# ArmRobot.net
KiCad netlist of a schematic drawn in EasyEDA Pro
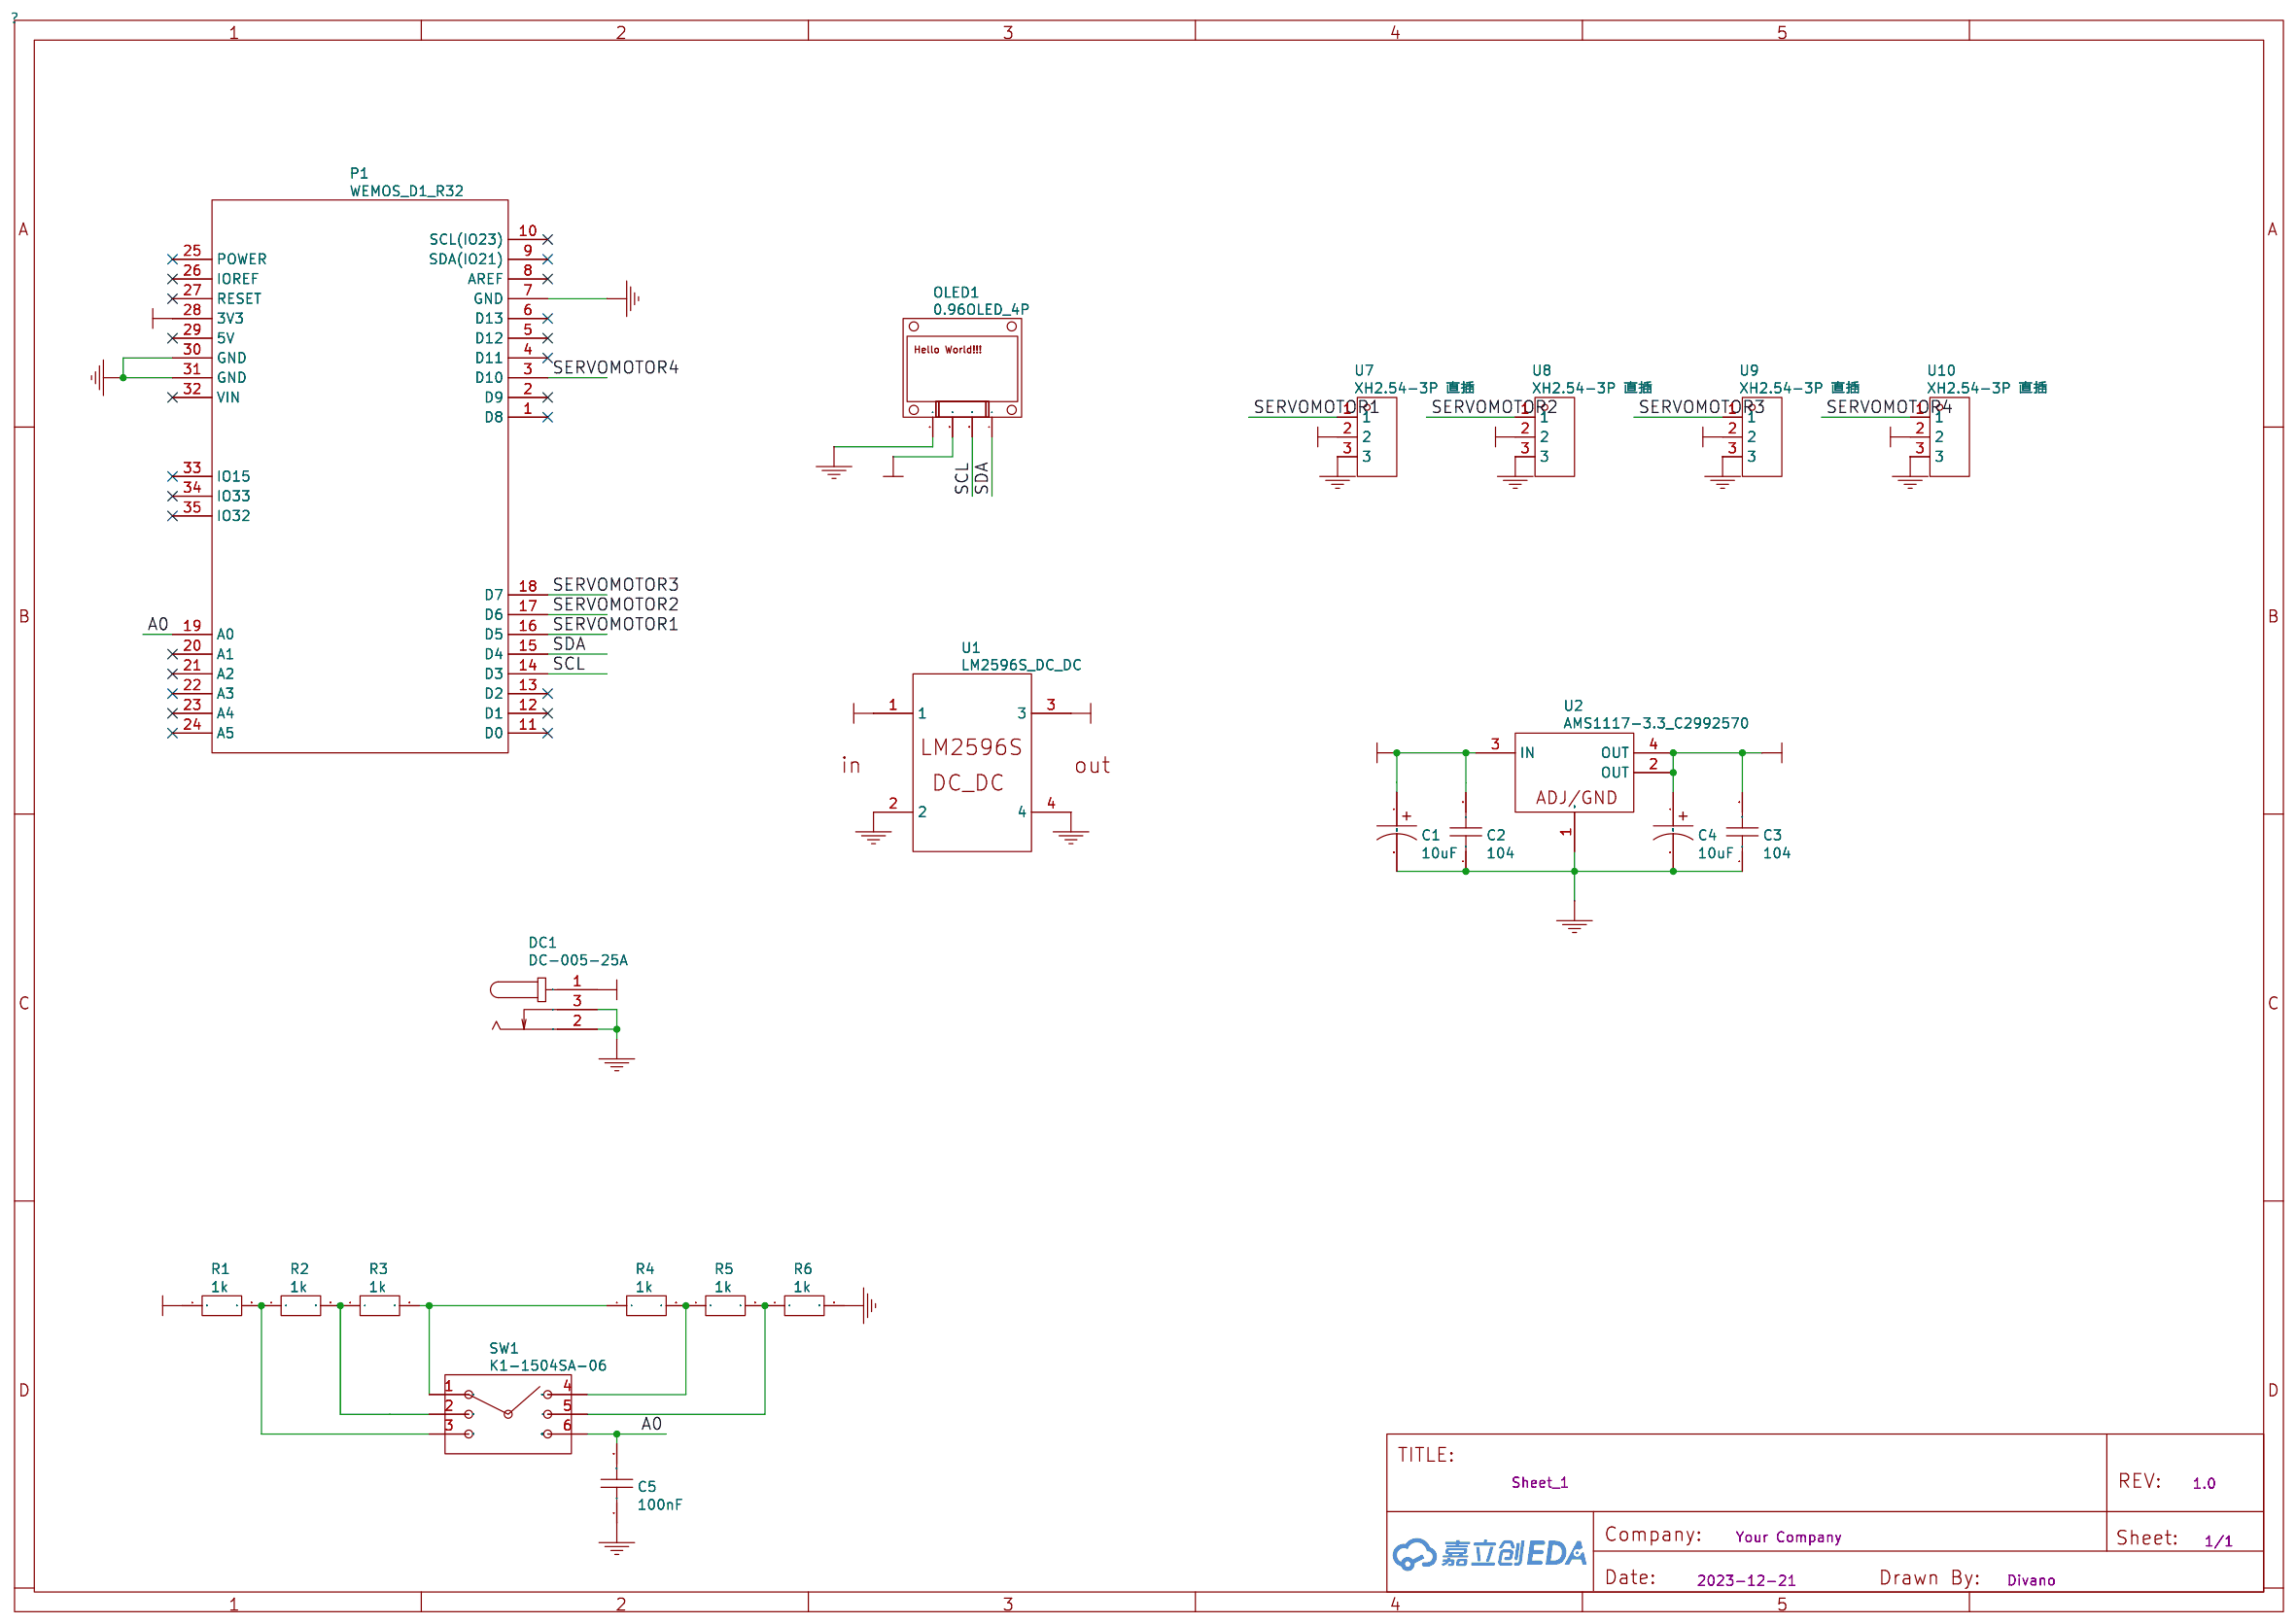
[diagram p0: schematic sheet]

(export (version "E")
  (design (tool "Eeschema 10.0.6"))
  (components
    (comp (ref "C1")
      (value "10uF")
      (footprint "easyedapro:CASE-A_3216")
      (libsource (lib "easyedapro") (part "10uF"))
    )
    (comp (ref "C2") (value "104") (footprint "easyedapro:C0805") (libsource (lib "easyedapro") (part "104")))
    (comp (ref "C3") (value "104") (footprint "easyedapro:C0805") (libsource (lib "easyedapro") (part "104")))
    (comp (ref "C4")
      (value "10uF")
      (footprint "easyedapro:CASE-A_3216")
      (libsource (lib "easyedapro") (part "10uF"))
    )
    (comp (ref "C5")
      (value "100nF")
      (footprint "easyedapro:C0805")
      (libsource (lib "easyedapro") (part "100nF"))
    )
    (comp (ref "DC1")
      (value "DC-005-25A")
      (footprint "easyedapro:DC-IN-TH_DC005")
      (fields (field (name "Manufacturer") "HRO"))
      (libsource (lib "easyedapro") (part "DC-005-25A"))
    )
    (comp (ref "OLED1")
      (value "0.96OLED_4P")
      (footprint "easyedapro:0.96OLED_4P")
      (libsource (lib "easyedapro") (part "0.96OLED_4P"))
    )
    (comp (ref "P1")
      (value "WEMOS_D1_R32")
      (footprint "easyedapro:WEMOS_D1_R32")
      (fields (field (name "Manufacturer Part") "NA"))
      (libsource (lib "easyedapro") (part "WEMOS_D1_R32"))
    )
    (comp (ref "R1") (value "1k") (footprint "easyedapro:R0805") (libsource (lib "easyedapro") (part "1k")))
    (comp (ref "R2") (value "1k") (footprint "easyedapro:R0805") (libsource (lib "easyedapro") (part "1k")))
    (comp (ref "R3") (value "1k") (footprint "easyedapro:R0805") (libsource (lib "easyedapro") (part "1k")))
    (comp (ref "R4") (value "1k") (footprint "easyedapro:R0805") (libsource (lib "easyedapro") (part "1k")))
    (comp (ref "R5") (value "1k") (footprint "easyedapro:R0805") (libsource (lib "easyedapro") (part "1k")))
    (comp (ref "R6") (value "1k") (footprint "easyedapro:R0805") (libsource (lib "easyedapro") (part "1k")))
    (comp (ref "SW1")
      (value "K1-1504SA-06")
      (footprint "easyedapro:SW-SMD_K1-1504SA-06")
      (fields (field (name "Manufacturer") "韩国韩荣"))
      (libsource (lib "easyedapro") (part "K1-1504SA-06"))
    )
    (comp (ref "U1")
      (value "LM2596S_DC_DC")
      (footprint "easyedapro:LM2596S_DC_DC")
      (libsource (lib "easyedapro") (part "LM2596S_DC_DC"))
    )
    (comp (ref "U2")
      (value "AMS1117-3.3_C2992570")
      (footprint "easyedapro:SOT-223-3_L6.4-W3.5-P2.30-LS7.0-BR")
      (fields (field (name "Manufacturer Part") "AMS1117-3.3") (field (name "Manufacturer") "国芯佳品"))
      (libsource (lib "easyedapro") (part "AMS1117-3.3_C2992570"))
    )
    (comp (ref "U7")
      (value "XH2.54-3P 直插")
      (footprint "easyedapro:CONN-TH_XH2.54-3P")
      (libsource (lib "easyedapro") (part "XH2.54-3P 直插"))
    )
    (comp (ref "U8")
      (value "XH2.54-3P 直插")
      (footprint "easyedapro:CONN-TH_XH2.54-3P")
      (libsource (lib "easyedapro") (part "XH2.54-3P 直插"))
    )
    (comp (ref "U9")
      (value "XH2.54-3P 直插")
      (footprint "easyedapro:CONN-TH_XH2.54-3P")
      (libsource (lib "easyedapro") (part "XH2.54-3P 直插"))
    )
    (comp (ref "U10")
      (value "XH2.54-3P 直插")
      (footprint "easyedapro:CONN-TH_XH2.54-3P")
      (libsource (lib "easyedapro") (part "XH2.54-3P 直插"))
    )
  )
  (nets
    (net (code "1") (name "+3.3V") (class "Default")
      (node (ref "C3") (pin "2") (pinfunction "2_2") (pintype "input"))
      (node (ref "C4") (pin "1") (pinfunction "1_1") (pintype "input"))
      (node (ref "OLED1") (pin "2") (pinfunction "2_2") (pintype "input"))
      (node (ref "P1") (pin "28") (pinfunction "3V3_28") (pintype "input"))
      (node (ref "R1") (pin "1") (pinfunction "1_1") (pintype "input"))
      (node (ref "U2") (pin "2") (pinfunction "OUT_2") (pintype "input"))
      (node (ref "U2") (pin "4") (pinfunction "OUT_4") (pintype "input"))
    )
    (net (code "2") (name "+5V") (class "Default")
      (node (ref "C1") (pin "1") (pinfunction "1_1") (pintype "input"))
      (node (ref "C2") (pin "2") (pinfunction "2_2") (pintype "input"))
      (node (ref "U1") (pin "3") (pinfunction "3_3") (pintype "input"))
      (node (ref "U10") (pin "2") (pinfunction "2_2") (pintype "input"))
      (node (ref "U2") (pin "3") (pinfunction "IN_3") (pintype "input"))
      (node (ref "U7") (pin "2") (pinfunction "2_2") (pintype "input"))
      (node (ref "U8") (pin "2") (pinfunction "2_2") (pintype "input"))
      (node (ref "U9") (pin "2") (pinfunction "2_2") (pintype "input"))
    )
    (net (code "3") (name "+12V") (class "Default")
      (node (ref "DC1") (pin "1") (pinfunction "1_1") (pintype "input"))
      (node (ref "U1") (pin "1") (pinfunction "1_1") (pintype "input"))
    )
    (net (code "4") (name "/A0") (class "Default")
      (node (ref "C5") (pin "2") (pinfunction "2_2") (pintype "input"))
      (node (ref "P1") (pin "19") (pinfunction "A0_19") (pintype "input"))
      (node (ref "SW1") (pin "6") (pinfunction "COMMON_6") (pintype "input"))
    )
    (net (code "5") (name "/SCL") (class "Default")
      (node (ref "OLED1") (pin "3") (pinfunction "3_3") (pintype "input"))
      (node (ref "P1") (pin "14") (pinfunction "D3_14") (pintype "input"))
    )
    (net (code "6") (name "/SDA") (class "Default")
      (node (ref "OLED1") (pin "4") (pinfunction "4_4") (pintype "input"))
      (node (ref "P1") (pin "15") (pinfunction "D4_15") (pintype "input"))
    )
    (net (code "7") (name "/SERVOMOTOR1") (class "Default")
      (node (ref "P1") (pin "16") (pinfunction "D5_16") (pintype "input"))
      (node (ref "U7") (pin "1") (pinfunction "1_1") (pintype "input"))
    )
    (net (code "8") (name "/SERVOMOTOR2") (class "Default")
      (node (ref "P1") (pin "17") (pinfunction "D6_17") (pintype "input"))
      (node (ref "U8") (pin "1") (pinfunction "1_1") (pintype "input"))
    )
    (net (code "9") (name "/SERVOMOTOR3") (class "Default")
      (node (ref "P1") (pin "18") (pinfunction "D7_18") (pintype "input"))
      (node (ref "U9") (pin "1") (pinfunction "1_1") (pintype "input"))
    )
    (net (code "10") (name "/SERVOMOTOR4") (class "Default")
      (node (ref "P1") (pin "3") (pinfunction "D10_3") (pintype "input"))
      (node (ref "U10") (pin "1") (pinfunction "1_1") (pintype "input"))
    )
    (net (code "11") (name "GND") (class "Default")
      (node (ref "C1") (pin "2") (pinfunction "2_2") (pintype "input"))
      (node (ref "C2") (pin "1") (pinfunction "1_1") (pintype "input"))
      (node (ref "C3") (pin "1") (pinfunction "1_1") (pintype "input"))
      (node (ref "C4") (pin "2") (pinfunction "2_2") (pintype "input"))
      (node (ref "C5") (pin "1") (pinfunction "1_1") (pintype "input"))
      (node (ref "DC1") (pin "2") (pinfunction "2_2") (pintype "input"))
      (node (ref "DC1") (pin "3") (pinfunction "3_3") (pintype "input"))
      (node (ref "OLED1") (pin "1") (pinfunction "1_1") (pintype "input"))
      (node (ref "P1") (pin "30") (pinfunction "GND_30") (pintype "input"))
      (node (ref "P1") (pin "31") (pinfunction "GND_31") (pintype "input"))
      (node (ref "P1") (pin "7") (pinfunction "GND_7") (pintype "input"))
      (node (ref "R6") (pin "2") (pinfunction "2_2") (pintype "input"))
      (node (ref "U1") (pin "2") (pinfunction "2_2") (pintype "input"))
      (node (ref "U1") (pin "4") (pinfunction "4_4") (pintype "input"))
      (node (ref "U10") (pin "3") (pinfunction "3_3") (pintype "input"))
      (node (ref "U2") (pin "1") (pinfunction "ADJ/GND_1") (pintype "input"))
      (node (ref "U7") (pin "3") (pinfunction "3_3") (pintype "input"))
      (node (ref "U8") (pin "3") (pinfunction "3_3") (pintype "input"))
      (node (ref "U9") (pin "3") (pinfunction "3_3") (pintype "input"))
    )
    (net (code "12") (name "Net-(SW1-A)") (class "Default")
      (node (ref "R3") (pin "2") (pinfunction "2_2") (pintype "input"))
      (node (ref "R4") (pin "1") (pinfunction "1_1") (pintype "input"))
      (node (ref "SW1") (pin "1") (pinfunction "A_1") (pintype "input"))
    )
    (net (code "13") (name "Net-(SW1-B)") (class "Default")
      (node (ref "R2") (pin "2") (pinfunction "2_2") (pintype "input"))
      (node (ref "R3") (pin "1") (pinfunction "1_1") (pintype "input"))
      (node (ref "SW1") (pin "2") (pinfunction "B_2") (pintype "input"))
    )
    (net (code "14") (name "Net-(SW1-C)") (class "Default")
      (node (ref "R1") (pin "2") (pinfunction "2_2") (pintype "input"))
      (node (ref "R2") (pin "1") (pinfunction "1_1") (pintype "input"))
      (node (ref "SW1") (pin "3") (pinfunction "C_3") (pintype "input"))
    )
    (net (code "15") (name "Net-(SW1-CENTER)") (class "Default")
      (node (ref "R4") (pin "2") (pinfunction "2_2") (pintype "input"))
      (node (ref "R5") (pin "1") (pinfunction "1_1") (pintype "input"))
      (node (ref "SW1") (pin "4") (pinfunction "CENTER_4") (pintype "input"))
    )
    (net (code "16") (name "Net-(SW1-D)") (class "Default")
      (node (ref "R5") (pin "2") (pinfunction "2_2") (pintype "input"))
      (node (ref "R6") (pin "1") (pinfunction "1_1") (pintype "input"))
      (node (ref "SW1") (pin "5") (pinfunction "D_5") (pintype "input"))
    )
    (net (code "17") (name "unconnected-(P1-5V-Pad29)") (class "Default")
      (node (ref "P1") (pin "29") (pinfunction "5V_29") (pintype "input+no_connect"))
    )
    (net (code "18") (name "unconnected-(P1-A1-Pad20)") (class "Default")
      (node (ref "P1") (pin "20") (pinfunction "A1_20") (pintype "input+no_connect"))
    )
    (net (code "19") (name "unconnected-(P1-A2-Pad21)") (class "Default")
      (node (ref "P1") (pin "21") (pinfunction "A2_21") (pintype "input+no_connect"))
    )
    (net (code "20") (name "unconnected-(P1-A3-Pad22)") (class "Default")
      (node (ref "P1") (pin "22") (pinfunction "A3_22") (pintype "input+no_connect"))
    )
    (net (code "21") (name "unconnected-(P1-A4-Pad23)") (class "Default")
      (node (ref "P1") (pin "23") (pinfunction "A4_23") (pintype "input+no_connect"))
    )
    (net (code "22") (name "unconnected-(P1-A5-Pad24)") (class "Default")
      (node (ref "P1") (pin "24") (pinfunction "A5_24") (pintype "input+no_connect"))
    )
    (net (code "23") (name "unconnected-(P1-AREF-Pad8)") (class "Default")
      (node (ref "P1") (pin "8") (pinfunction "AREF_8") (pintype "input+no_connect"))
    )
    (net (code "24") (name "unconnected-(P1-D0-Pad11)") (class "Default")
      (node (ref "P1") (pin "11") (pinfunction "D0_11") (pintype "input+no_connect"))
    )
    (net (code "25") (name "unconnected-(P1-D1-Pad12)") (class "Default")
      (node (ref "P1") (pin "12") (pinfunction "D1_12") (pintype "input+no_connect"))
    )
    (net (code "26") (name "unconnected-(P1-D2-Pad13)") (class "Default")
      (node (ref "P1") (pin "13") (pinfunction "D2_13") (pintype "input+no_connect"))
    )
    (net (code "27") (name "unconnected-(P1-D8-Pad1)") (class "Default")
      (node (ref "P1") (pin "1") (pinfunction "D8_1") (pintype "input+no_connect"))
    )
    (net (code "28") (name "unconnected-(P1-D9-Pad2)") (class "Default")
      (node (ref "P1") (pin "2") (pinfunction "D9_2") (pintype "input+no_connect"))
    )
    (net (code "29") (name "unconnected-(P1-D11-Pad4)") (class "Default")
      (node (ref "P1") (pin "4") (pinfunction "D11_4") (pintype "input+no_connect"))
    )
    (net (code "30") (name "unconnected-(P1-D12-Pad5)") (class "Default")
      (node (ref "P1") (pin "5") (pinfunction "D12_5") (pintype "input+no_connect"))
    )
    (net (code "31") (name "unconnected-(P1-D13-Pad6)") (class "Default")
      (node (ref "P1") (pin "6") (pinfunction "D13_6") (pintype "input+no_connect"))
    )
    (net (code "32") (name "unconnected-(P1-IO15-Pad33)") (class "Default")
      (node (ref "P1") (pin "33") (pinfunction "IO15_33") (pintype "input+no_connect"))
    )
    (net (code "33") (name "unconnected-(P1-IO32-Pad35)") (class "Default")
      (node (ref "P1") (pin "35") (pinfunction "IO32_35") (pintype "input+no_connect"))
    )
    (net (code "34") (name "unconnected-(P1-IO33-Pad34)") (class "Default")
      (node (ref "P1") (pin "34") (pinfunction "IO33_34") (pintype "input+no_connect"))
    )
    (net (code "35") (name "unconnected-(P1-IOREF-Pad26)") (class "Default")
      (node (ref "P1") (pin "26") (pinfunction "IOREF_26") (pintype "input+no_connect"))
    )
    (net (code "36") (name "unconnected-(P1-POWER-Pad25)") (class "Default")
      (node (ref "P1") (pin "25") (pinfunction "POWER_25") (pintype "input+no_connect"))
    )
    (net (code "37") (name "unconnected-(P1-RESET-Pad27)") (class "Default")
      (node (ref "P1") (pin "27") (pinfunction "RESET_27") (pintype "input+no_connect"))
    )
    (net (code "38") (name "unconnected-(P1-SCL(IO23)-Pad10)") (class "Default")
      (node (ref "P1") (pin "10") (pinfunction "SCL(IO23)_10") (pintype "input+no_connect"))
    )
    (net (code "39") (name "unconnected-(P1-SDA(IO21)-Pad9)") (class "Default")
      (node (ref "P1") (pin "9") (pinfunction "SDA(IO21)_9") (pintype "input+no_connect"))
    )
    (net (code "40") (name "unconnected-(P1-VIN-Pad32)") (class "Default")
      (node (ref "P1") (pin "32") (pinfunction "VIN_32") (pintype "input+no_connect"))
    )
  )
)
